# Cyber_VCM.net
KiCad netlist of a schematic drawn in Altium Designer
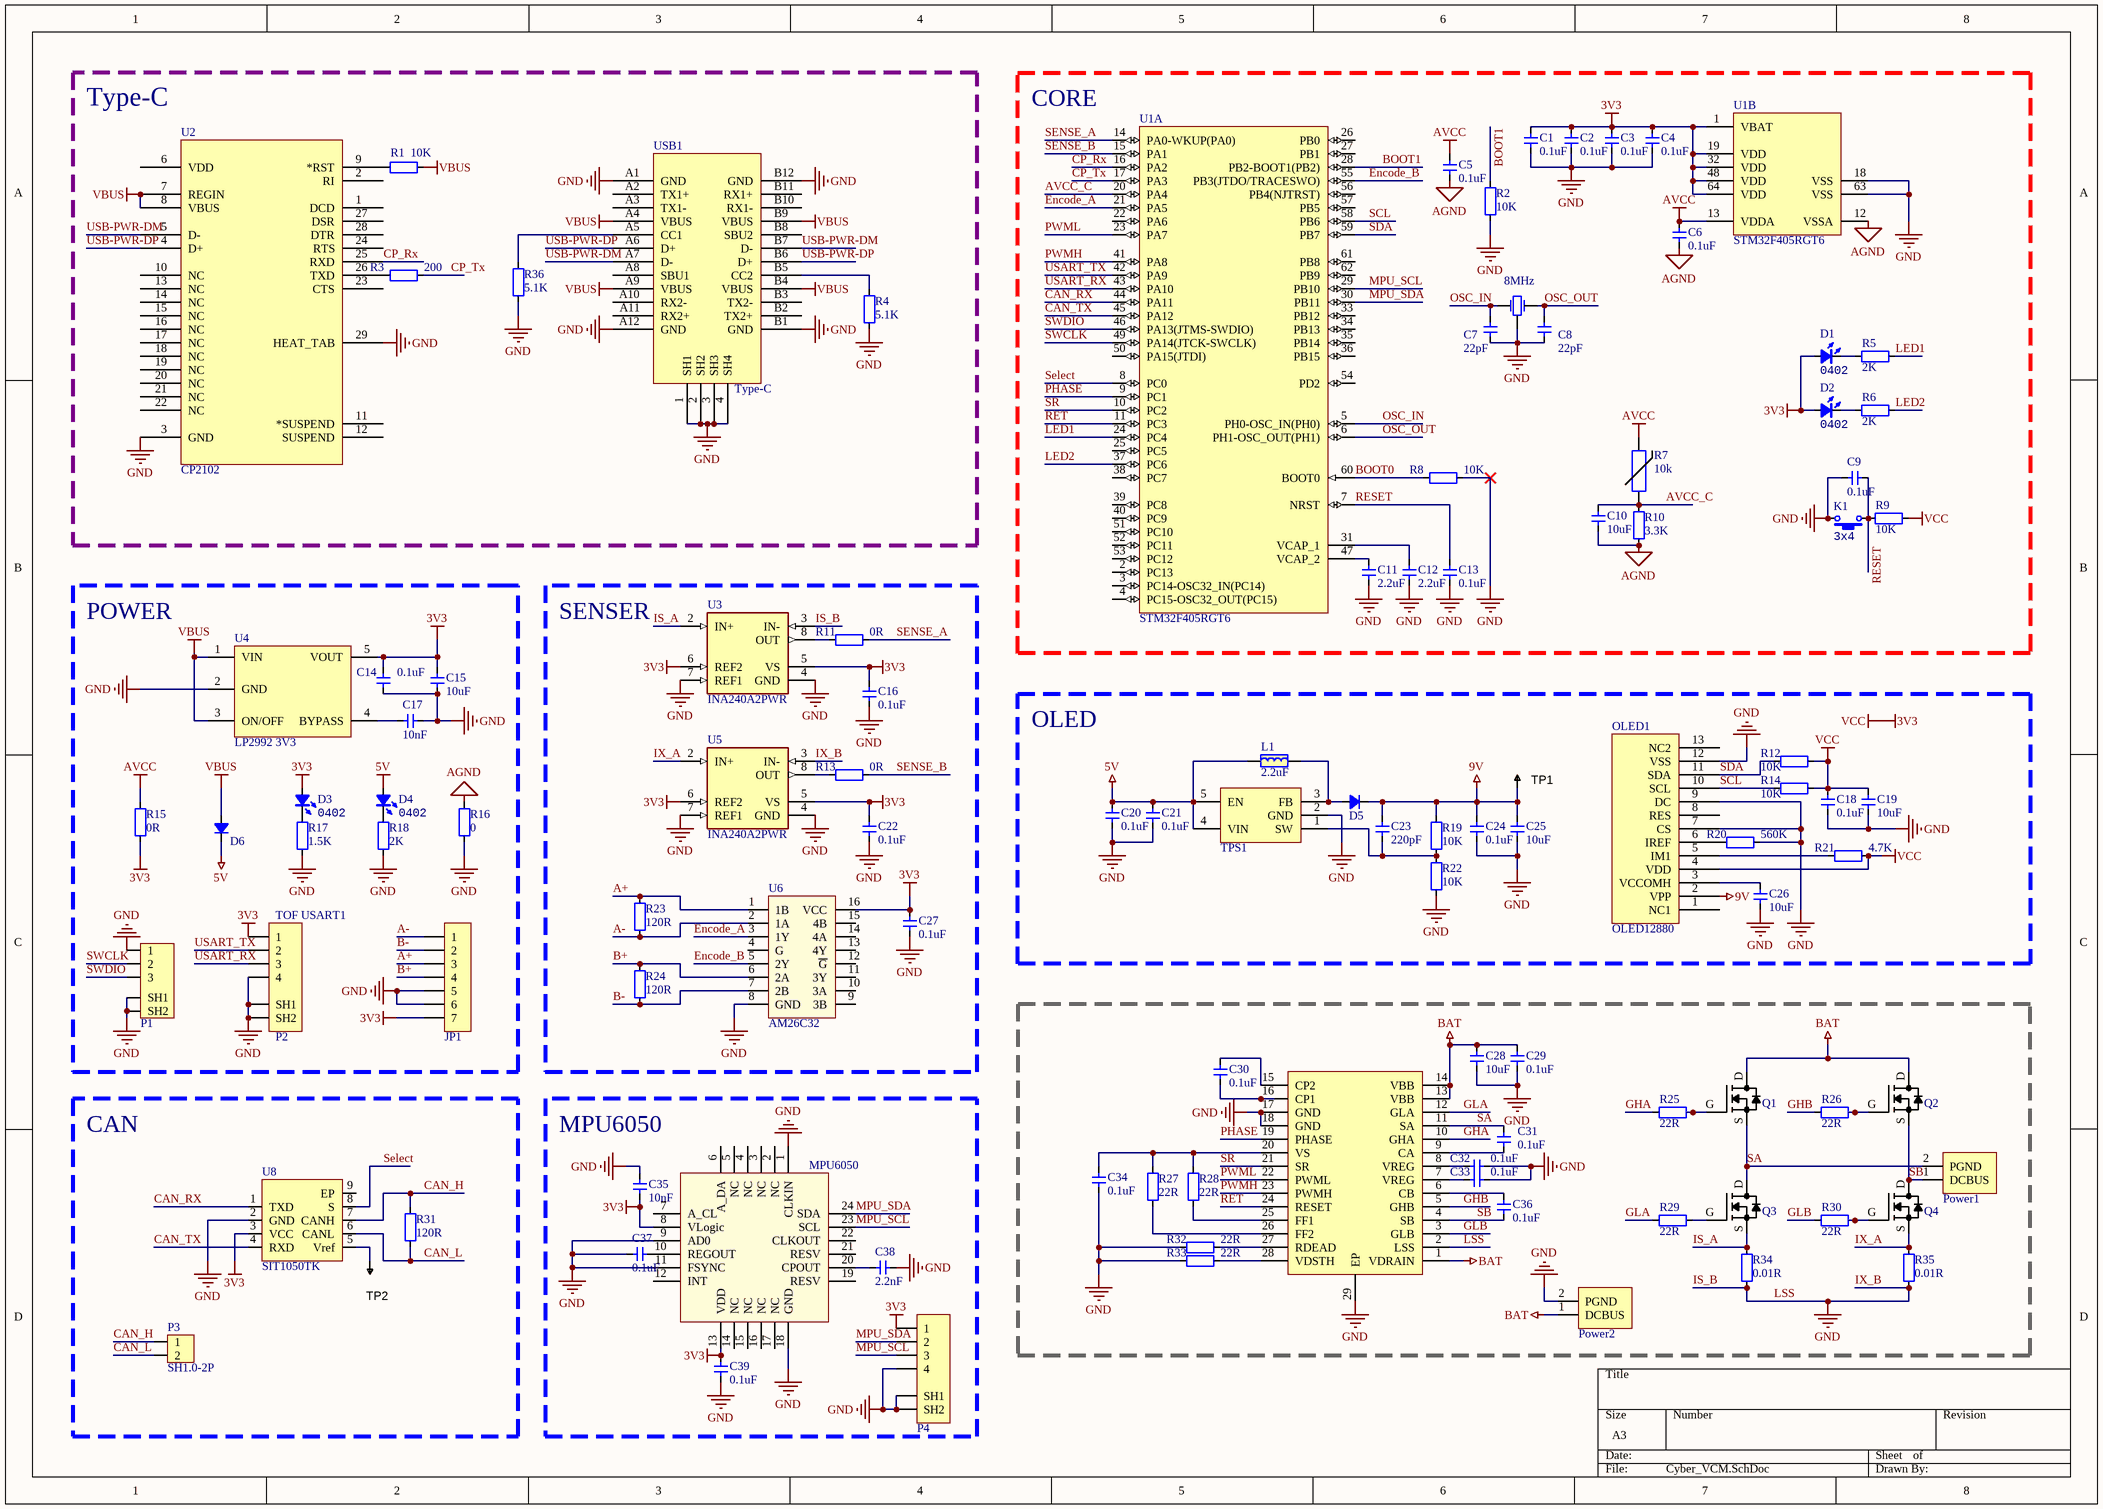
[diagram p0: Cyber_VCM.SchDoc]

(export (version "E")
  (design (tool "Eeschema 10.0.6"))
  (components
    (comp (ref "*1") (value "A3941") (footprint "TSSOP28_n") (libsource (lib "Cyber_VCM") (part "A3941")))
    (comp (ref "C1")
      (value "0.1uF")
      (footprint "CAP_0402")
      (description "Capacitor")
      (libsource (lib "VectorController") (part "电容-0402"))
    )
    (comp (ref "C2")
      (value "0.1uF")
      (footprint "CAP_0402")
      (description "Capacitor")
      (libsource (lib "VectorController") (part "电容-0402"))
    )
    (comp (ref "C3")
      (value "0.1uF")
      (footprint "CAP_0402")
      (description "Capacitor")
      (libsource (lib "VectorController") (part "电容-0402"))
    )
    (comp (ref "C4")
      (value "0.1uF")
      (footprint "CAP_0402")
      (description "Capacitor")
      (libsource (lib "VectorController") (part "电容-0402"))
    )
    (comp (ref "C5")
      (value "0.1uF")
      (footprint "0603-CAP")
      (description "Capacitor")
      (libsource (lib "Ctrl_FOC") (part "电容-0603"))
    )
    (comp (ref "C6")
      (value "0.1uF")
      (footprint "0603-CAP")
      (description "Capacitor")
      (libsource (lib "Ctrl_FOC") (part "电容-0603"))
    )
    (comp (ref "C7")
      (value "22pF")
      (footprint "CAP_0402")
      (description "Capacitor")
      (libsource (lib "Ctrl_FOC") (part "电容-0402"))
    )
    (comp (ref "C8")
      (value "22pF")
      (footprint "CAP_0402")
      (description "Capacitor")
      (libsource (lib "Ctrl_FOC") (part "电容-0402"))
    )
    (comp (ref "C9")
      (value "0.1uF")
      (footprint "CAP_0402")
      (description "Capacitor")
      (libsource (lib "VectorController") (part "电容-0402"))
    )
    (comp (ref "C10")
      (value "10uF")
      (footprint "CAP_0402")
      (description "Capacitor")
      (libsource (lib "MyPcbLib") (part "电容-0402"))
    )
    (comp (ref "C11")
      (value "2.2uF")
      (footprint "CAP_0402")
      (description "Capacitor")
      (libsource (lib "Ctrl_FOC") (part "电容-0402"))
    )
    (comp (ref "C12")
      (value "2.2uF")
      (footprint "CAP_0402")
      (description "Capacitor")
      (libsource (lib "Ctrl_FOC") (part "电容-0402"))
    )
    (comp (ref "C13")
      (value "0.1uF")
      (footprint "CAP_0402")
      (description "Capacitor")
      (libsource (lib "Ctrl_FOC") (part "电容-0402"))
    )
    (comp (ref "C14")
      (value "0.1uF")
      (footprint "CAP_0402")
      (description "Capacitor")
      (libsource (lib "Cyber_VCM") (part "电容-0402"))
    )
    (comp (ref "C15")
      (value "10uF")
      (footprint "CAP_0402")
      (description "Capacitor")
      (libsource (lib "Cyber_VCM") (part "电容-0402"))
    )
    (comp (ref "C16")
      (value "0.1uF")
      (footprint "CAP_0402")
      (description "Capacitor")
      (libsource (lib "MyPcbLib") (part "电容-0402"))
    )
    (comp (ref "C17")
      (value "10nF")
      (footprint "CAP_0402")
      (description "Capacitor")
      (libsource (lib "Cyber_VCM") (part "电容-0402"))
    )
    (comp (ref "C18")
      (value "0.1uF")
      (footprint "CAP_0402")
      (description "Capacitor")
      (libsource (lib "Serena-Ctrl") (part "电容-0402"))
    )
    (comp (ref "C19")
      (value "10uF")
      (footprint "CAP_0402")
      (description "Capacitor")
      (libsource (lib "Serena-Ctrl") (part "电容-0402"))
    )
    (comp (ref "C20")
      (value "0.1uF")
      (footprint "CAP_0402")
      (description "Capacitor")
      (libsource (lib "Serena-Ctrl") (part "电容-0402"))
    )
    (comp (ref "C21")
      (value "0.1uF")
      (footprint "CAP_0402")
      (description "Capacitor")
      (libsource (lib "Serena-Ctrl") (part "电容-0402"))
    )
    (comp (ref "C22")
      (value "0.1uF")
      (footprint "CAP_0402")
      (description "Capacitor")
      (libsource (lib "MyPcbLib") (part "电容-0402"))
    )
    (comp (ref "C23")
      (value "220pF")
      (footprint "CAP_0402")
      (description "Capacitor")
      (libsource (lib "Serena-Ctrl") (part "电容-0402"))
    )
    (comp (ref "C24")
      (value "0.1uF")
      (footprint "0603-CAP")
      (description "Capacitor")
      (libsource (lib "Serena-Ctrl") (part "电容-0603"))
    )
    (comp (ref "C25")
      (value "10uF")
      (footprint "0603-CAP")
      (description "Capacitor")
      (libsource (lib "Serena-Ctrl") (part "电容-0603"))
    )
    (comp (ref "C26")
      (value "10uF")
      (footprint "CAP_0402")
      (description "Capacitor")
      (libsource (lib "Serena-Ctrl") (part "电容-0402"))
    )
    (comp (ref "C27")
      (value "0.1uF")
      (footprint "0603-CAP")
      (description "Capacitor")
      (libsource (lib "VCM_Ctrl") (part "电容-0603"))
    )
    (comp (ref "C28")
      (value "10uF")
      (footprint "2520-L")
      (description "Capacitor")
      (libsource (lib "Cyber_VCM") (part "电容-1206"))
    )
    (comp (ref "C29")
      (value "0.1uF")
      (footprint "2520-L")
      (description "Capacitor")
      (libsource (lib "Cyber_VCM") (part "电容-1206"))
    )
    (comp (ref "C30")
      (value "0.1uF")
      (footprint "0603-CAP")
      (description "Capacitor")
      (libsource (lib "Cyber_VCM") (part "电容-0603"))
    )
    (comp (ref "C31")
      (value "0.1uF")
      (footprint "CAP_0402")
      (description "Capacitor")
      (libsource (lib "Cyber_VCM") (part "电容-0402"))
    )
    (comp (ref "C32")
      (value "0.1uF")
      (footprint "CAP_0402")
      (description "Capacitor")
      (libsource (lib "Cyber_VCM") (part "电容-0402"))
    )
    (comp (ref "C33")
      (value "0.1uF")
      (footprint "CAP_0402")
      (description "Capacitor")
      (libsource (lib "Cyber_VCM") (part "电容-0402"))
    )
    (comp (ref "C34")
      (value "0.1uF")
      (footprint "0603-CAP")
      (description "Capacitor")
      (libsource (lib "Cyber_VCM") (part "电容-0603"))
    )
    (comp (ref "C35")
      (value "10nF")
      (footprint "CAP_0402")
      (description "Capacitor")
      (libsource (lib "MyPcbLib") (part "电容-0402"))
    )
    (comp (ref "C36")
      (value "0.1uF")
      (footprint "CAP_0402")
      (description "Capacitor")
      (libsource (lib "Cyber_VCM") (part "电容-0402"))
    )
    (comp (ref "C37")
      (value "0.1uF")
      (footprint "CAP_0402")
      (description "Capacitor")
      (libsource (lib "MyPcbLib") (part "电容-0402"))
    )
    (comp (ref "C38")
      (value "2.2nF")
      (footprint "CAP_0402")
      (description "Capacitor")
      (libsource (lib "MyPcbLib") (part "电容-0402"))
    )
    (comp (ref "C39")
      (value "0.1uF")
      (footprint "CAP_0402")
      (description "Capacitor")
      (libsource (lib "MyPcbLib") (part "电容-0402"))
    )
    (comp (ref "D1")
      (value "color?")
      (footprint "LED_0402_BLUE")
      (description "LED")
      (fields (field (name "TYPE") "0402"))
      (libsource (lib "Cyber_VCM") (part "LED_0402"))
    )
    (comp (ref "D2")
      (value "color?")
      (footprint "LED_0402_BLUE")
      (description "LED")
      (fields (field (name "TYPE") "0402"))
      (libsource (lib "Cyber_VCM") (part "LED_0402"))
    )
    (comp (ref "D3")
      (value "color?")
      (footprint "LED_0402_BLUE")
      (description "LED")
      (fields (field (name "TYPE") "0402"))
      (libsource (lib "") (part "LED_0402_1"))
    )
    (comp (ref "D4")
      (value "color?")
      (footprint "LED_0402_BLUE")
      (description "LED")
      (fields (field (name "TYPE") "0402"))
      (libsource (lib "") (part "LED_0402_1"))
    )
    (comp (ref "D5")
      (value "二极管-5819W")
      (footprint "SOD-123")
      (description "40V")
      (libsource (lib "Cyber_VCM") (part "二极管-5819W"))
    )
    (comp (ref "D6")
      (value "二极管-5819W")
      (footprint "SOD-123")
      (description "40V")
      (libsource (lib "Cyber_VCM") (part "二极管-5819W"))
    )
    (comp (ref "JP1")
      (value "SH1.0-7P")
      (footprint "SH1.0-7P-L")
      (libsource (lib "Cyber_VCM") (part "SH1.0-7P"))
    )
    (comp (ref "K1")
      (value "3x4")
      (footprint "ButtonTACT_3x4x2_180")
      (description "Button")
      (fields (field (name "Comment") "TACT 2P"))
      (libsource (lib "Ctrl_FOC") (part "ButtonTACT_3x4x2_180"))
    )
    (comp (ref "L1")
      (value "2.2uF")
      (footprint "2520-L")
      (description "磁珠")
      (libsource (lib "Serena-Ctrl") (part "电感-0805"))
    )
    (comp (ref "OLED1")
      (value "OLED12880")
      (footprint "OLED12880")
      (description "12880寸OLED")
      (libsource (lib "Serena-Ctrl") (part "OLED12880"))
    )
    (comp (ref "P1")
      (value "SH1.0-3P")
      (footprint "SH1.0-3P")
      (description "Header")
      (libsource (lib "Cyber_VCM") (part "SH1.0-3P"))
    )
    (comp (ref "P2")
      (value "TOF USART1")
      (footprint "SH1.0-4P")
      (libsource (lib "Cyber_VCM") (part "SH1.0-4P"))
    )
    (comp (ref "P3")
      (value "SH1.0-2P")
      (footprint "SH1.0-2P")
      (libsource (lib "Cyber_VCM") (part "SH1.0-2P"))
    )
    (comp (ref "P4")
      (value "SH1.0-4P")
      (footprint "SH1.0-4P")
      (libsource (lib "Cyber_VCM") (part "SH1.0-4P"))
    )
    (comp (ref "Power1")
      (value "电源")
      (footprint "音圈电机电源接口")
      (description "12~24VDC电源")
      (libsource (lib "Cyber_VCM") (part "电源"))
    )
    (comp (ref "Power2")
      (value "电源")
      (footprint "TX60电源")
      (description "12~24VDC电源")
      (libsource (lib "Cyber_VCM") (part "电源"))
    )
    (comp (ref "Q1")
      (value "NTMFS4935NT1G")
      (footprint "SO8FL")
      (description "MOSFET N-CH 30V 13A SO8FL")
      (fields (field (name "MANUFACTURER") "ON Semiconductor"))
      (libsource (lib "Cyber_VCM") (part "NTMFS4935NT1G"))
    )
    (comp (ref "Q2")
      (value "NTMFS4935NT1G")
      (footprint "SO8FL")
      (description "MOSFET N-CH 30V 13A SO8FL")
      (fields (field (name "MANUFACTURER") "ON Semiconductor"))
      (libsource (lib "Cyber_VCM") (part "NTMFS4935NT1G"))
    )
    (comp (ref "Q3")
      (value "NTMFS4935NT1G")
      (footprint "SO8FL")
      (description "MOSFET N-CH 30V 13A SO8FL")
      (fields (field (name "MANUFACTURER") "ON Semiconductor"))
      (libsource (lib "Cyber_VCM") (part "NTMFS4935NT1G"))
    )
    (comp (ref "Q4")
      (value "NTMFS4935NT1G")
      (footprint "SO8FL")
      (description "MOSFET N-CH 30V 13A SO8FL")
      (fields (field (name "MANUFACTURER") "ON Semiconductor"))
      (libsource (lib "Cyber_VCM") (part "NTMFS4935NT1G"))
    )
    (comp (ref "R1")
      (value "10K")
      (footprint "RES_0402")
      (description "Resistor")
      (libsource (lib "MyPcbLib") (part "电阻-0402"))
    )
    (comp (ref "R2")
      (value "10K")
      (footprint "RES_0402")
      (description "Resistor")
      (libsource (lib "") (part "电阻-0402_1"))
    )
    (comp (ref "R3")
      (value "200")
      (footprint "RES_0402")
      (description "Resistor")
      (libsource (lib "MyPcbLib") (part "电阻-0402"))
    )
    (comp (ref "R4")
      (value "5.1K")
      (footprint "RES_0402")
      (description "Resistor")
      (libsource (lib "") (part "电阻-0402_1"))
    )
    (comp (ref "R5")
      (value "2K")
      (footprint "RES_0402")
      (description "Resistor")
      (libsource (lib "") (part "电阻-0402_1"))
    )
    (comp (ref "R6")
      (value "2K")
      (footprint "RES_0402")
      (description "Resistor")
      (libsource (lib "") (part "电阻-0402_1"))
    )
    (comp (ref "R7")
      (value "10k")
      (footprint "RES_0402")
      (description "THERMISTOR 10K OHM NTC 0402 SMD")
      (fields (field (name "Comment") "NCP15XH103F03RC"))
      (libsource (lib "MyPcbLib") (part "NCP15XH103F03RC"))
    )
    (comp (ref "R8")
      (value "10K")
      (footprint "RES_0402")
      (description "Resistor")
      (libsource (lib "Ctrl_FOC") (part "电阻-0402"))
    )
    (comp (ref "R9")
      (value "10K")
      (footprint "RES_0402")
      (description "Resistor")
      (libsource (lib "Ctrl_FOC") (part "电阻-0402"))
    )
    (comp (ref "R10")
      (value "3.3K")
      (footprint "RES_0402")
      (description "Resistor")
      (libsource (lib "") (part "电阻-0402_3"))
    )
    (comp (ref "R11")
      (value "0R")
      (footprint "RES_0402")
      (description "Resistor")
      (libsource (lib "") (part "电阻-0402_2"))
    )
    (comp (ref "R12")
      (value "10K")
      (footprint "RES_0402")
      (description "Resistor")
      (libsource (lib "") (part "电阻-0402_1"))
    )
    (comp (ref "R13")
      (value "0R")
      (footprint "RES_0402")
      (description "Resistor")
      (libsource (lib "") (part "电阻-0402_2"))
    )
    (comp (ref "R14")
      (value "10K")
      (footprint "RES_0402")
      (description "Resistor")
      (libsource (lib "") (part "电阻-0402_1"))
    )
    (comp (ref "R15")
      (value "0R")
      (footprint "RES_0402")
      (description "Resistor")
      (libsource (lib "") (part "电阻-0402_1"))
    )
    (comp (ref "R16")
      (value "0")
      (footprint "RES_0402")
      (description "Resistor")
      (libsource (lib "") (part "电阻-0402_2"))
    )
    (comp (ref "R17")
      (value "1.5K")
      (footprint "RES_0402")
      (description "Resistor")
      (libsource (lib "") (part "电阻-0402_2"))
    )
    (comp (ref "R18")
      (value "2K")
      (footprint "RES_0402")
      (description "Resistor")
      (libsource (lib "") (part "电阻-0402_2"))
    )
    (comp (ref "R19")
      (value "10K")
      (footprint "RES_0402")
      (description "Resistor")
      (libsource (lib "Serena-Ctrl") (part "电阻-0402"))
    )
    (comp (ref "R20")
      (value "560K")
      (footprint "RES_0402")
      (description "Resistor")
      (libsource (lib "") (part "电阻-0402_1"))
    )
    (comp (ref "R21")
      (value "4.7K")
      (footprint "RES_0402")
      (description "Resistor")
      (libsource (lib "") (part "电阻-0402_1"))
    )
    (comp (ref "R22")
      (value "10K")
      (footprint "RES_0402")
      (description "Resistor")
      (libsource (lib "Serena-Ctrl") (part "电阻-0402"))
    )
    (comp (ref "R23")
      (value "120R")
      (footprint "RES_0603")
      (description "Resistor")
      (libsource (lib "Ctrl_FOC") (part "电阻-0603"))
    )
    (comp (ref "R24")
      (value "120R")
      (footprint "RES_0603")
      (description "Resistor")
      (libsource (lib "Ctrl_FOC") (part "电阻-0603"))
    )
    (comp (ref "R25")
      (value "22R")
      (footprint "RES_0402")
      (description "Resistor")
      (libsource (lib "") (part "电阻-0402_1"))
    )
    (comp (ref "R26")
      (value "22R")
      (footprint "RES_0402")
      (description "Resistor")
      (libsource (lib "") (part "电阻-0402_1"))
    )
    (comp (ref "R27")
      (value "22R")
      (footprint "RES_0402")
      (description "Resistor")
      (libsource (lib "Cyber_VCM") (part "电阻-0402"))
    )
    (comp (ref "R28")
      (value "22R")
      (footprint "RES_0402")
      (description "Resistor")
      (libsource (lib "Cyber_VCM") (part "电阻-0402"))
    )
    (comp (ref "R29")
      (value "22R")
      (footprint "RES_0402")
      (description "Resistor")
      (libsource (lib "") (part "电阻-0402_1"))
    )
    (comp (ref "R30")
      (value "22R")
      (footprint "RES_0402")
      (description "Resistor")
      (libsource (lib "") (part "电阻-0402_1"))
    )
    (comp (ref "R31")
      (value "120R")
      (footprint "RES_0402")
      (description "Resistor")
      (libsource (lib "Cyber_VCM") (part "电阻-0402"))
    )
    (comp (ref "R32")
      (value "22R")
      (footprint "RES_0402")
      (description "Resistor")
      (libsource (lib "") (part "电阻-0402_1"))
    )
    (comp (ref "R33")
      (value "22R")
      (footprint "RES_0402")
      (description "Resistor")
      (libsource (lib "") (part "电阻-0402_1"))
    )
    (comp (ref "R34")
      (value "0.01R")
      (footprint "1206-RES")
      (description "Resistor")
      (libsource (lib "Cyber_VCM") (part "电阻-1206"))
    )
    (comp (ref "R35")
      (value "0.01R")
      (footprint "1206-RES")
      (description "Resistor")
      (libsource (lib "Cyber_VCM") (part "电阻-1206"))
    )
    (comp (ref "R36")
      (value "5.1K")
      (footprint "RES_0402")
      (description "Resistor")
      (libsource (lib "") (part "电阻-0402_1"))
    )
    (comp (ref "TP1")
      (value "TESTPOINT")
      (footprint "TP-R30")
      (description "SMD test pin")
      (libsource (lib "Serena-Ctrl") (part "TESTPOINT"))
    )
    (comp (ref "TP2")
      (value "TESTPOINT")
      (footprint "TP-R30")
      (description "SMD test pin")
      (libsource (lib "Serena-Ctrl") (part "TESTPOINT"))
    )
    (comp (ref "TPS1")
      (value "TPS61040DBV")
      (footprint "SOT23-5")
      (libsource (lib "Serena-Ctrl") (part "TPS61040DBV"))
    )
    (comp (ref "U1")
      (value "STM32F405RGT6")
      (footprint "主控芯片LQFP64-10*10")
      (fields (field (name "MANUFACTURER") "STMicroelectronics"))
      (libsource (lib "VectorController") (part "STM32F405RGT6"))
    )
    (comp (ref "U2")
      (value "CP2102")
      (footprint "QFN-28")
      (description "USB转TTL")
      (libsource (lib "Cyber_VCM") (part "CP2102"))
    )
    (comp (ref "U3")
      (value "INA240A2PWR")
      (footprint "SOP65 P640X120-8N")
      (fields (field (name "MF") "Texas Instruments"))
      (libsource (lib "mLib") (part "INA240A2PWR"))
    )
    (comp (ref "U4")
      (value "LP2992 3V3")
      (footprint "SOT23-5")
      (description "LDO")
      (libsource (lib "Cyber_VCM") (part "LP2992"))
    )
    (comp (ref "U5")
      (value "INA240A2PWR")
      (footprint "SOP65 P640X120-8N")
      (fields (field (name "MF") "Texas Instruments"))
      (libsource (lib "mLib") (part "INA240A2PWR"))
    )
    (comp (ref "U6")
      (value "AM26C32")
      (footprint "SOP16")
      (description "AM26C32 Quadruple Differential Line Receiver")
      (libsource (lib "VCM_Ctrl") (part "AM26C32"))
    )
    (comp (ref "U7")
      (value "MPU6050")
      (footprint "QFN-24")
      (description "六轴传感器")
      (libsource (lib "mLib") (part "MPU6050"))
    )
    (comp (ref "U8")
      (value "SIT1050TK")
      (footprint "DFN3x3-8")
      (description "CAN收发器，DFN3x3-8")
      (libsource (lib "Cyber_VCM") (part "SIT1050TK"))
    )
    (comp (ref "USB1")
      (value "Type-C")
      (footprint "Type-C-TOP")
      (libsource (lib "Cyber_VCM") (part "USB-Type-C-TOP"))
    )
    (comp (ref "X1") (value "8MHz") (footprint "晶振-3P") (libsource (lib "MiniFly ") (part "XTAL-3215")))
  )
  (nets
    (net (code "1") (name "/A+") (class "Default")
      (node (ref "JP1") (pin "3") (pinfunction "3_3") (pintype "passive"))
      (node (ref "R23") (pin "2") (pinfunction "2_2") (pintype "passive"))
      (node (ref "U6") (pin "1") (pinfunction "1B_1") (pintype "passive"))
    )
    (net (code "2") (name "/A-") (class "Default")
      (node (ref "JP1") (pin "1") (pinfunction "1_1") (pintype "passive"))
      (node (ref "R23") (pin "1") (pinfunction "1_1") (pintype "passive"))
      (node (ref "U6") (pin "2") (pinfunction "1A_2") (pintype "passive"))
    )
    (net (code "3") (name "/AVCC_C") (class "Default")
      (node (ref "C10") (pin "2") (pinfunction "2_2") (pintype "passive"))
      (node (ref "R10") (pin "2") (pinfunction "2_2") (pintype "passive"))
      (node (ref "R7") (pin "1") (pinfunction "0_1") (pintype "passive"))
      (node (ref "U1") (pin "20") (pinfunction "PA4_20") (pintype "bidirectional"))
    )
    (net (code "4") (name "/B+") (class "Default")
      (node (ref "JP1") (pin "4") (pinfunction "4_4") (pintype "passive"))
      (node (ref "R24") (pin "2") (pinfunction "2_2") (pintype "passive"))
      (node (ref "U6") (pin "6") (pinfunction "2A_6") (pintype "passive"))
    )
    (net (code "5") (name "/B-") (class "Default")
      (node (ref "JP1") (pin "2") (pinfunction "2_2") (pintype "passive"))
      (node (ref "R24") (pin "1") (pinfunction "1_1") (pintype "passive"))
      (node (ref "U6") (pin "7") (pinfunction "2B_7") (pintype "passive"))
    )
    (net (code "6") (name "/BOOT0") (class "Default")
      (node (ref "R8") (pin "2") (pinfunction "2_2") (pintype "passive"))
      (node (ref "U1") (pin "60") (pinfunction "BOOT0_60") (pintype "input"))
    )
    (net (code "7") (name "/BOOT1") (class "Default")
      (node (ref "R2") (pin "2") (pinfunction "2_2") (pintype "passive"))
      (node (ref "U1") (pin "28") (pinfunction "PB2-BOOT1(PB2)_28") (pintype "bidirectional"))
    )
    (net (code "8") (name "/CAN_H") (class "Default")
      (node (ref "P3") (pin "1") (pinfunction "1_1") (pintype "passive"))
      (node (ref "R31") (pin "2") (pinfunction "2_2") (pintype "passive"))
      (node (ref "U8") (pin "7") (pinfunction "CANH_7") (pintype "passive"))
    )
    (net (code "9") (name "/CAN_L") (class "Default")
      (node (ref "P3") (pin "2") (pinfunction "2_2") (pintype "passive"))
      (node (ref "R31") (pin "1") (pinfunction "1_1") (pintype "passive"))
      (node (ref "U8") (pin "6") (pinfunction "CANL_6") (pintype "passive"))
    )
    (net (code "10") (name "/CAN_RX") (class "Default")
      (node (ref "U1") (pin "44") (pinfunction "PA11_44") (pintype "bidirectional"))
      (node (ref "U8") (pin "1") (pinfunction "TXD_1") (pintype "passive"))
    )
    (net (code "11") (name "/CAN_TX") (class "Default")
      (node (ref "U1") (pin "45") (pinfunction "PA12_45") (pintype "bidirectional"))
      (node (ref "U8") (pin "4") (pinfunction "RXD_4") (pintype "passive"))
    )
    (net (code "12") (name "/CP_Rx") (class "Default")
      (node (ref "U1") (pin "16") (pinfunction "PA2_16") (pintype "bidirectional"))
      (node (ref "U2") (pin "25") (pinfunction "RXD_25") (pintype "passive"))
    )
    (net (code "13") (name "/CP_Tx") (class "Default")
      (node (ref "R3") (pin "1") (pinfunction "1_1") (pintype "passive"))
      (node (ref "U1") (pin "17") (pinfunction "PA3_17") (pintype "bidirectional"))
    )
    (net (code "14") (name "/Encode_A") (class "Default")
      (node (ref "U1") (pin "21") (pinfunction "PA5_21") (pintype "bidirectional"))
      (node (ref "U6") (pin "3") (pinfunction "1Y_3") (pintype "passive"))
    )
    (net (code "15") (name "/Encode_B") (class "Default")
      (node (ref "U1") (pin "55") (pinfunction "PB3(JTDO/TRACESWO)_55") (pintype "bidirectional"))
      (node (ref "U6") (pin "5") (pinfunction "2Y_5") (pintype "passive"))
    )
    (net (code "16") (name "/GHA") (class "Default")
      (node (ref "*1") (pin "10") (pinfunction "GHA_10") (pintype "passive"))
      (node (ref "R25") (pin "1") (pinfunction "1_1") (pintype "passive"))
    )
    (net (code "17") (name "/GHB") (class "Default")
      (node (ref "*1") (pin "5") (pinfunction "GHB_5") (pintype "passive"))
      (node (ref "R26") (pin "1") (pinfunction "1_1") (pintype "passive"))
    )
    (net (code "18") (name "/GLA") (class "Default")
      (node (ref "*1") (pin "12") (pinfunction "GLA_12") (pintype "passive"))
      (node (ref "R29") (pin "1") (pinfunction "1_1") (pintype "passive"))
    )
    (net (code "19") (name "/GLB") (class "Default")
      (node (ref "*1") (pin "3") (pinfunction "GLB_3") (pintype "passive"))
      (node (ref "R30") (pin "1") (pinfunction "1_1") (pintype "passive"))
    )
    (net (code "20") (name "/IS_A") (class "Default")
      (node (ref "Q3") (pin "S") (pinfunction "S_S") (pintype "passive"))
      (node (ref "R34") (pin "2") (pinfunction "2_2") (pintype "passive"))
      (node (ref "U3") (pin "2") (pinfunction "IN+_2") (pintype "input"))
    )
    (net (code "21") (name "/IX_A") (class "Default")
      (node (ref "Q4") (pin "S") (pinfunction "S_S") (pintype "passive"))
      (node (ref "R35") (pin "2") (pinfunction "2_2") (pintype "passive"))
      (node (ref "U5") (pin "2") (pinfunction "IN+_2") (pintype "input"))
    )
    (net (code "22") (name "/LED1") (class "Default")
      (node (ref "R5") (pin "2") (pinfunction "2_2") (pintype "passive"))
      (node (ref "U1") (pin "24") (pinfunction "PC4_24") (pintype "bidirectional"))
    )
    (net (code "23") (name "/LED2") (class "Default")
      (node (ref "R6") (pin "2") (pinfunction "2_2") (pintype "passive"))
      (node (ref "U1") (pin "37") (pinfunction "PC6_37") (pintype "bidirectional"))
    )
    (net (code "24") (name "/MPU_SCL") (class "Default")
      (node (ref "P4") (pin "3") (pinfunction "3_3") (pintype "passive"))
      (node (ref "U1") (pin "29") (pinfunction "PB10_29") (pintype "bidirectional"))
      (node (ref "U7") (pin "23") (pinfunction "SCL_23") (pintype "passive"))
    )
    (net (code "25") (name "/MPU_SDA") (class "Default")
      (node (ref "P4") (pin "2") (pinfunction "2_2") (pintype "passive"))
      (node (ref "U1") (pin "30") (pinfunction "PB11_30") (pintype "bidirectional"))
      (node (ref "U7") (pin "24") (pinfunction "SDA_24") (pintype "passive"))
    )
    (net (code "26") (name "/OSC_IN") (class "Default")
      (node (ref "C7") (pin "2") (pinfunction "2_2") (pintype "passive"))
      (node (ref "U1") (pin "5") (pinfunction "PH0-OSC_IN(PH0)_5") (pintype "bidirectional"))
      (node (ref "X1") (pin "1") (pinfunction "OSC1_1") (pintype "passive"))
    )
    (net (code "27") (name "/OSC_OUT") (class "Default")
      (node (ref "C8") (pin "2") (pinfunction "2_2") (pintype "passive"))
      (node (ref "U1") (pin "6") (pinfunction "PH1-OSC_OUT(PH1)_6") (pintype "bidirectional"))
      (node (ref "X1") (pin "3") (pinfunction "OSC2_3") (pintype "passive"))
    )
    (net (code "28") (name "/PHASE") (class "Default")
      (node (ref "*1") (pin "19") (pinfunction "PHASE_19") (pintype "passive"))
      (node (ref "U1") (pin "9") (pinfunction "PC1_9") (pintype "bidirectional"))
    )
    (net (code "29") (name "/PWMH") (class "Default")
      (node (ref "*1") (pin "23") (pinfunction "PWMH_23") (pintype "passive"))
      (node (ref "U1") (pin "41") (pinfunction "PA8_41") (pintype "bidirectional"))
    )
    (net (code "30") (name "/PWML") (class "Default")
      (node (ref "*1") (pin "22") (pinfunction "PWML_22") (pintype "passive"))
      (node (ref "U1") (pin "23") (pinfunction "PA7_23") (pintype "bidirectional"))
    )
    (net (code "31") (name "/RESET") (class "Default")
      (node (ref "C13") (pin "1") (pinfunction "1_1") (pintype "passive"))
      (node (ref "C9") (pin "2") (pinfunction "2_2") (pintype "passive"))
      (node (ref "K1") (pin "1") (pinfunction "1_1") (pintype "passive"))
      (node (ref "R9") (pin "2") (pinfunction "2_2") (pintype "passive"))
      (node (ref "U1") (pin "7") (pinfunction "NRST_7") (pintype "bidirectional"))
    )
    (net (code "32") (name "/RET") (class "Default")
      (node (ref "*1") (pin "24") (pinfunction "RESET_24") (pintype "passive"))
      (node (ref "U1") (pin "11") (pinfunction "PC3_11") (pintype "bidirectional"))
    )
    (net (code "33") (name "/SA") (class "Default")
      (node (ref "*1") (pin "11") (pinfunction "SA_11") (pintype "passive"))
      (node (ref "C31") (pin "2") (pinfunction "2_2") (pintype "passive"))
      (node (ref "Power1") (pin "2") (pinfunction "PGND_2") (pintype "passive"))
      (node (ref "Q1") (pin "S") (pinfunction "S_S") (pintype "passive"))
      (node (ref "Q3") (pin "D") (pinfunction "D_D") (pintype "passive"))
    )
    (net (code "34") (name "/SB") (class "Default")
      (node (ref "*1") (pin "4") (pinfunction "SB_4") (pintype "passive"))
      (node (ref "C36") (pin "1") (pinfunction "1_1") (pintype "passive"))
      (node (ref "Power1") (pin "1") (pinfunction "DCBUS_1") (pintype "passive"))
      (node (ref "Q2") (pin "S") (pinfunction "S_S") (pintype "passive"))
      (node (ref "Q4") (pin "D") (pinfunction "D_D") (pintype "passive"))
    )
    (net (code "35") (name "/SCL") (class "Default")
      (node (ref "OLED1") (pin "10") (pinfunction "SCL_10") (pintype "passive"))
      (node (ref "R14") (pin "1") (pinfunction "1_1") (pintype "passive"))
      (node (ref "U1") (pin "58") (pinfunction "PB6_58") (pintype "bidirectional"))
    )
    (net (code "36") (name "/SDA") (class "Default")
      (node (ref "OLED1") (pin "11") (pinfunction "SDA_11") (pintype "passive"))
      (node (ref "R12") (pin "1") (pinfunction "1_1") (pintype "passive"))
      (node (ref "U1") (pin "59") (pinfunction "PB7_59") (pintype "bidirectional"))
    )
    (net (code "37") (name "/SENSE_A") (class "Default")
      (node (ref "R11") (pin "2") (pinfunction "2_2") (pintype "passive"))
      (node (ref "U1") (pin "14") (pinfunction "PA0-WKUP(PA0)_14") (pintype "bidirectional"))
    )
    (net (code "38") (name "/SENSE_B") (class "Default")
      (node (ref "R13") (pin "2") (pinfunction "2_2") (pintype "passive"))
      (node (ref "U1") (pin "15") (pinfunction "PA1_15") (pintype "bidirectional"))
    )
    (net (code "39") (name "/SR") (class "Default")
      (node (ref "*1") (pin "21") (pinfunction "SR_21") (pintype "passive"))
      (node (ref "U1") (pin "10") (pinfunction "PC2_10") (pintype "bidirectional"))
    )
    (net (code "40") (name "/SWCLK") (class "Default")
      (node (ref "P1") (pin "2") (pinfunction "2_2") (pintype "passive"))
      (node (ref "U1") (pin "49") (pinfunction "PA14(JTCK-SWCLK)_49") (pintype "bidirectional"))
    )
    (net (code "41") (name "/SWDIO") (class "Default")
      (node (ref "P1") (pin "3") (pinfunction "3_3") (pintype "passive"))
      (node (ref "U1") (pin "46") (pinfunction "PA13(JTMS-SWDIO)_46") (pintype "bidirectional"))
    )
    (net (code "42") (name "/Select") (class "Default")
      (node (ref "U1") (pin "8") (pinfunction "PC0_8") (pintype "bidirectional"))
      (node (ref "U8") (pin "8") (pinfunction "S_8") (pintype "passive"))
    )
    (net (code "43") (name "/USART_RX") (class "Default")
      (node (ref "P2") (pin "3") (pinfunction "3_3") (pintype "passive"))
      (node (ref "U1") (pin "43") (pinfunction "PA10_43") (pintype "bidirectional"))
    )
    (net (code "44") (name "/USART_TX") (class "Default")
      (node (ref "P2") (pin "2") (pinfunction "2_2") (pintype "passive"))
      (node (ref "U1") (pin "42") (pinfunction "PA9_42") (pintype "bidirectional"))
    )
    (net (code "45") (name "/USB-PWR-DM") (class "Default")
      (node (ref "U2") (pin "5") (pinfunction "D-_5") (pintype "passive"))
      (node (ref "USB1") (pin "A7") (pinfunction "D-_A7") (pintype "passive"))
      (node (ref "USB1") (pin "B7") (pinfunction "D-_B7") (pintype "passive"))
    )
    (net (code "46") (name "/USB-PWR-DP") (class "Default")
      (node (ref "U2") (pin "4") (pinfunction "D+_4") (pintype "passive"))
      (node (ref "USB1") (pin "A6") (pinfunction "D+_A6") (pintype "passive"))
      (node (ref "USB1") (pin "B6") (pinfunction "D+_B6") (pintype "passive"))
    )
    (net (code "47") (name "3V3") (class "Default")
      (node (ref "C1") (pin "2") (pinfunction "2_2") (pintype "passive"))
      (node (ref "C14") (pin "2") (pinfunction "2_2") (pintype "passive"))
      (node (ref "C15") (pin "2") (pinfunction "2_2") (pintype "passive"))
      (node (ref "C16") (pin "2") (pinfunction "2_2") (pintype "passive"))
      (node (ref "C18") (pin "2") (pinfunction "2_2") (pintype "passive"))
      (node (ref "C19") (pin "2") (pinfunction "2_2") (pintype "passive"))
      (node (ref "C2") (pin "2") (pinfunction "2_2") (pintype "passive"))
      (node (ref "C22") (pin "2") (pinfunction "2_2") (pintype "passive"))
      (node (ref "C27") (pin "2") (pinfunction "2_2") (pintype "passive"))
      (node (ref "C3") (pin "2") (pinfunction "2_2") (pintype "passive"))
      (node (ref "C35") (pin "1") (pinfunction "1_1") (pintype "passive"))
      (node (ref "C39") (pin "2") (pinfunction "2_2") (pintype "passive"))
      (node (ref "C4") (pin "2") (pinfunction "2_2") (pintype "passive"))
      (node (ref "D1") (pin "1") (pinfunction "A_1") (pintype "passive"))
      (node (ref "D2") (pin "1") (pinfunction "A_1") (pintype "passive"))
      (node (ref "D3") (pin "1") (pinfunction "A_1") (pintype "passive"))
      (node (ref "JP1") (pin "7") (pinfunction "7_7") (pintype "passive"))
      (node (ref "OLED1") (pin "4") (pinfunction "VDD_4") (pintype "passive"))
      (node (ref "P2") (pin "1") (pinfunction "1_1") (pintype "passive"))
      (node (ref "P4") (pin "1") (pinfunction "1_1") (pintype "passive"))
      (node (ref "R12") (pin "2") (pinfunction "2_2") (pintype "passive"))
      (node (ref "R14") (pin "2") (pinfunction "2_2") (pintype "passive"))
      (node (ref "R15") (pin "2") (pinfunction "2_2") (pintype "passive"))
      (node (ref "R21") (pin "2") (pinfunction "2_2") (pintype "passive"))
      (node (ref "R9") (pin "1") (pinfunction "1_1") (pintype "passive"))
      (node (ref "U1") (pin "1") (pinfunction "VBAT_1") (pintype "power_in"))
      (node (ref "U1") (pin "19") (pinfunction "VDD_19") (pintype "power_in"))
      (node (ref "U1") (pin "32") (pinfunction "VDD_32") (pintype "power_in"))
      (node (ref "U1") (pin "48") (pinfunction "VDD_48") (pintype "power_in"))
      (node (ref "U1") (pin "64") (pinfunction "VDD_64") (pintype "power_in"))
      (node (ref "U3") (pin "5") (pinfunction "VS_5") (pintype "power_in"))
      (node (ref "U3") (pin "6") (pinfunction "REF2_6") (pintype "input"))
      (node (ref "U4") (pin "5") (pinfunction "VOUT_5") (pintype "passive"))
      (node (ref "U5") (pin "5") (pinfunction "VS_5") (pintype "power_in"))
      (node (ref "U5") (pin "6") (pinfunction "REF2_6") (pintype "input"))
      (node (ref "U6") (pin "16") (pinfunction "VCC_16") (pintype "passive"))
      (node (ref "U7") (pin "13") (pinfunction "VDD_13") (pintype "passive"))
      (node (ref "U7") (pin "8") (pinfunction "VLogic_8") (pintype "passive"))
      (node (ref "U8") (pin "3") (pinfunction "VCC_3") (pintype "passive"))
    )
    (net (code "48") (name "5V") (class "Default")
      (node (ref "C20") (pin "2") (pinfunction "2_2") (pintype "passive"))
      (node (ref "C21") (pin "2") (pinfunction "2_2") (pintype "passive"))
      (node (ref "D4") (pin "1") (pinfunction "A_1") (pintype "passive"))
      (node (ref "D6") (pin "2") (pinfunction "K_2") (pintype "passive"))
      (node (ref "L1") (pin "1") (pintype "passive"))
      (node (ref "TPS1") (pin "4") (pinfunction "VIN_4") (pintype "passive"))
      (node (ref "TPS1") (pin "5") (pinfunction "EN_5") (pintype "passive"))
    )
    (net (code "49") (name "9V") (class "Default")
      (node (ref "C23") (pin "2") (pinfunction "2_2") (pintype "passive"))
      (node (ref "C24") (pin "2") (pinfunction "2_2") (pintype "passive"))
      (node (ref "C25") (pin "2") (pinfunction "2_2") (pintype "passive"))
      (node (ref "D5") (pin "2") (pinfunction "K_2") (pintype "passive"))
      (node (ref "OLED1") (pin "2") (pinfunction "VPP_2") (pintype "passive"))
      (node (ref "R19") (pin "2") (pinfunction "2_2") (pintype "passive"))
      (node (ref "TP1") (pin "1") (pintype "passive"))
    )
    (net (code "50") (name "AGND") (class "Default")
      (node (ref "C10") (pin "1") (pinfunction "1_1") (pintype "passive"))
      (node (ref "C5") (pin "1") (pinfunction "1_1") (pintype "passive"))
      (node (ref "C6") (pin "1") (pinfunction "1_1") (pintype "passive"))
      (node (ref "R10") (pin "1") (pinfunction "1_1") (pintype "passive"))
      (node (ref "R16") (pin "1") (pinfunction "1_1") (pintype "passive"))
      (node (ref "U1") (pin "12") (pinfunction "VSSA_12") (pintype "power_in"))
    )
    (net (code "51") (name "AVCC") (class "Default")
      (node (ref "C5") (pin "2") (pinfunction "2_2") (pintype "passive"))
      (node (ref "C6") (pin "2") (pinfunction "2_2") (pintype "passive"))
      (node (ref "R15") (pin "1") (pinfunction "1_1") (pintype "passive"))
      (node (ref "R7") (pin "2") (pinfunction "0_2") (pintype "passive"))
      (node (ref "U1") (pin "13") (pinfunction "VDDA_13") (pintype "power_in"))
    )
    (net (code "52") (name "BAT") (class "Default")
      (node (ref "*1") (pin "1") (pinfunction "VDRAIN_1") (pintype "passive"))
      (node (ref "*1") (pin "13") (pinfunction "VBB_13") (pintype "passive"))
      (node (ref "*1") (pin "14") (pinfunction "VBB_14") (pintype "passive"))
      (node (ref "C28") (pin "2") (pinfunction "2_2") (pintype "passive"))
      (node (ref "C29") (pin "2") (pinfunction "2_2") (pintype "passive"))
      (node (ref "Power2") (pin "1") (pinfunction "DCBUS_1") (pintype "passive"))
      (node (ref "Q1") (pin "D") (pinfunction "D_D") (pintype "passive"))
      (node (ref "Q2") (pin "D") (pinfunction "D_D") (pintype "passive"))
    )
    (net (code "53") (name "GND") (class "Default")
      (node (ref "*1") (pin "17") (pinfunction "GND_17") (pintype "passive"))
      (node (ref "*1") (pin "18") (pinfunction "GND_18") (pintype "passive"))
      (node (ref "*1") (pin "2") (pinfunction "LSS_2") (pintype "passive"))
      (node (ref "*1") (pin "29") (pinfunction "EP_29") (pintype "passive"))
      (node (ref "C1") (pin "1") (pinfunction "1_1") (pintype "passive"))
      (node (ref "C11") (pin "1") (pinfunction "1_1") (pintype "passive"))
      (node (ref "C12") (pin "1") (pinfunction "1_1") (pintype "passive"))
      (node (ref "C13") (pin "2") (pinfunction "2_2") (pintype "passive"))
      (node (ref "C14") (pin "1") (pinfunction "1_1") (pintype "passive"))
      (node (ref "C15") (pin "1") (pinfunction "1_1") (pintype "passive"))
      (node (ref "C16") (pin "1") (pinfunction "1_1") (pintype "passive"))
      (node (ref "C17") (pin "2") (pinfunction "2_2") (pintype "passive"))
      (node (ref "C18") (pin "1") (pinfunction "1_1") (pintype "passive"))
      (node (ref "C19") (pin "1") (pinfunction "1_1") (pintype "passive"))
      (node (ref "C2") (pin "1") (pinfunction "1_1") (pintype "passive"))
      (node (ref "C20") (pin "1") (pinfunction "1_1") (pintype "passive"))
      (node (ref "C21") (pin "1") (pinfunction "1_1") (pintype "passive"))
      (node (ref "C22") (pin "1") (pinfunction "1_1") (pintype "passive"))
      (node (ref "C24") (pin "1") (pinfunction "1_1") (pintype "passive"))
      (node (ref "C25") (pin "1") (pinfunction "1_1") (pintype "passive"))
      (node (ref "C26") (pin "1") (pinfunction "1_1") (pintype "passive"))
      (node (ref "C27") (pin "1") (pinfunction "1_1") (pintype "passive"))
      (node (ref "C28") (pin "1") (pinfunction "1_1") (pintype "passive"))
      (node (ref "C29") (pin "1") (pinfunction "1_1") (pintype "passive"))
      (node (ref "C3") (pin "1") (pinfunction "1_1") (pintype "passive"))
      (node (ref "C32") (pin "1") (pinfunction "1_1") (pintype "passive"))
      (node (ref "C33") (pin "1") (pinfunction "1_1") (pintype "passive"))
      (node (ref "C34") (pin "1") (pinfunction "1_1") (pintype "passive"))
      (node (ref "C35") (pin "2") (pinfunction "2_2") (pintype "passive"))
      (node (ref "C37") (pin "2") (pinfunction "2_2") (pintype "passive"))
      (node (ref "C38") (pin "1") (pinfunction "1_1") (pintype "passive"))
      (node (ref "C39") (pin "1") (pinfunction "1_1") (pintype "passive"))
      (node (ref "C4") (pin "1") (pinfunction "1_1") (pintype "passive"))
      (node (ref "C7") (pin "1") (pinfunction "1_1") (pintype "passive"))
      (node (ref "C8") (pin "1") (pinfunction "1_1") (pintype "passive"))
      (node (ref "C9") (pin "1") (pinfunction "1_1") (pintype "passive"))
      (node (ref "JP1") (pin "5") (pinfunction "5_5") (pintype "passive"))
      (node (ref "JP1") (pin "6") (pinfunction "6_6") (pintype "passive"))
      (node (ref "K1") (pin "2") (pinfunction "2_2") (pintype "passive"))
      (node (ref "OLED1") (pin "12") (pinfunction "VSS_12") (pintype "passive"))
      (node (ref "OLED1") (pin "7") (pinfunction "CS_7") (pintype "passive"))
      (node (ref "OLED1") (pin "9") (pinfunction "DC_9") (pintype "passive"))
      (node (ref "P1") (pin "1") (pinfunction "1_1") (pintype "passive"))
      (node (ref "P1") (pin "SH1") (pinfunction "SH1_SH1") (pintype "passive"))
      (node (ref "P1") (pin "SH2") (pinfunction "SH2_SH2") (pintype "passive"))
      (node (ref "P2") (pin "4") (pinfunction "4_4") (pintype "passive"))
      (node (ref "P2") (pin "SH1") (pinfunction "SH1_SH1") (pintype "passive"))
      (node (ref "P2") (pin "SH2") (pinfunction "SH2_SH2") (pintype "passive"))
      (node (ref "P4") (pin "4") (pinfunction "4_4") (pintype "passive"))
      (node (ref "P4") (pin "SH1") (pinfunction "SH1_SH1") (pintype "passive"))
      (node (ref "P4") (pin "SH2") (pinfunction "SH2_SH2") (pintype "passive"))
      (node (ref "Power2") (pin "2") (pinfunction "PGND_2") (pintype "passive"))
      (node (ref "R16") (pin "2") (pinfunction "2_2") (pintype "passive"))
      (node (ref "R17") (pin "2") (pinfunction "2_2") (pintype "passive"))
      (node (ref "R18") (pin "2") (pinfunction "2_2") (pintype "passive"))
      (node (ref "R2") (pin "1") (pinfunction "1_1") (pintype "passive"))
      (node (ref "R20") (pin "2") (pinfunction "2_2") (pintype "passive"))
      (node (ref "R22") (pin "1") (pinfunction "1_1") (pintype "passive"))
      (node (ref "R32") (pin "1") (pinfunction "1_1") (pintype "passive"))
      (node (ref "R33") (pin "1") (pinfunction "1_1") (pintype "passive"))
      (node (ref "R34") (pin "1") (pinfunction "1_1") (pintype "passive"))
      (node (ref "R35") (pin "1") (pinfunction "1_1") (pintype "passive"))
      (node (ref "R36") (pin "2") (pinfunction "2_2") (pintype "passive"))
      (node (ref "R4") (pin "2") (pinfunction "2_2") (pintype "passive"))
      (node (ref "R8") (pin "1") (pinfunction "1_1") (pintype "passive"))
      (node (ref "TPS1") (pin "2") (pinfunction "GND_2") (pintype "passive"))
      (node (ref "U1") (pin "18") (pinfunction "VSS_18") (pintype "power_in"))
      (node (ref "U1") (pin "63") (pinfunction "VSS_63") (pintype "power_in"))
      (node (ref "U2") (pin "29") (pinfunction "HEAT_TAB_29") (pintype "passive"))
      (node (ref "U2") (pin "3") (pinfunction "GND_3") (pintype "passive"))
      (node (ref "U3") (pin "3") (pinfunction "IN-_3") (pintype "input"))
      (node (ref "U3") (pin "4") (pinfunction "GND_4") (pintype "power_in"))
      (node (ref "U3") (pin "7") (pinfunction "REF1_7") (pintype "input"))
      (node (ref "U4") (pin "2") (pinfunction "GND_2") (pintype "passive"))
      (node (ref "U5") (pin "3") (pinfunction "IN-_3") (pintype "input"))
      (node (ref "U5") (pin "4") (pinfunction "GND_4") (pintype "power_in"))
      (node (ref "U5") (pin "7") (pinfunction "REF1_7") (pintype "input"))
      (node (ref "U6") (pin "8") (pinfunction "GND_8") (pintype "passive"))
      (node (ref "U7") (pin "1") (pinfunction "CLKIN_1") (pintype "passive"))
      (node (ref "U7") (pin "11") (pinfunction "FSYNC_11") (pintype "passive"))
      (node (ref "U7") (pin "18") (pinfunction "GND_18") (pintype "passive"))
      (node (ref "U7") (pin "9") (pinfunction "AD0_9") (pintype "passive"))
      (node (ref "U8") (pin "2") (pinfunction "GND_2") (pintype "passive"))
      (node (ref "USB1") (pin "1") (pinfunction "SH1_1") (pintype "passive"))
      (node (ref "USB1") (pin "2") (pinfunction "SH2_2") (pintype "passive"))
      (node (ref "USB1") (pin "3") (pinfunction "SH3_3") (pintype "passive"))
      (node (ref "USB1") (pin "4") (pinfunction "SH4_4") (pintype "passive"))
      (node (ref "USB1") (pin "A1") (pinfunction "GND_A1") (pintype "passive"))
      (node (ref "USB1") (pin "A12") (pinfunction "GND_A12") (pintype "passive"))
      (node (ref "USB1") (pin "B1") (pinfunction "GND_B1") (pintype "passive"))
      (node (ref "USB1") (pin "B12") (pinfunction "GND_B12") (pintype "passive"))
      (node (ref "X1") (pin "2") (pinfunction "GND_2") (pintype "passive"))
    )
    (net (code "54") (name "Net-(*1-CA)") (class "Default")
      (node (ref "*1") (pin "9") (pinfunction "CA_9") (pintype "passive"))
      (node (ref "C31") (pin "1") (pinfunction "1_1") (pintype "passive"))
    )
    (net (code "55") (name "Net-(*1-CB)") (class "Default")
      (node (ref "*1") (pin "6") (pinfunction "CB_6") (pintype "passive"))
      (node (ref "C36") (pin "2") (pinfunction "2_2") (pintype "passive"))
    )
    (net (code "56") (name "Net-(*1-CP1)") (class "Default")
      (node (ref "*1") (pin "16") (pinfunction "CP1_16") (pintype "passive"))
      (node (ref "C30") (pin "1") (pinfunction "1_1") (pintype "passive"))
    )
    (net (code "57") (name "Net-(*1-CP2)") (class "Default")
      (node (ref "*1") (pin "15") (pinfunction "CP2_15") (pintype "passive"))
      (node (ref "C30") (pin "2") (pinfunction "2_2") (pintype "passive"))
    )
    (net (code "58") (name "Net-(*1-FF1)") (class "Default")
      (node (ref "*1") (pin "25") (pinfunction "FF1_25") (pintype "passive"))
      (node (ref "R28") (pin "1") (pinfunction "1_1") (pintype "passive"))
    )
    (net (code "59") (name "Net-(*1-FF2)") (class "Default")
      (node (ref "*1") (pin "26") (pinfunction "FF2_26") (pintype "passive"))
      (node (ref "R27") (pin "1") (pinfunction "1_1") (pintype "passive"))
    )
    (net (code "60") (name "Net-(*1-RDEAD)") (class "Default")
      (node (ref "*1") (pin "27") (pinfunction "RDEAD_27") (pintype "passive"))
      (node (ref "R32") (pin "2") (pinfunction "2_2") (pintype "passive"))
    )
    (net (code "61") (name "Net-(*1-VDSTH)") (class "Default")
      (node (ref "*1") (pin "28") (pinfunction "VDSTH_28") (pintype "passive"))
      (node (ref "R33") (pin "2") (pinfunction "2_2") (pintype "passive"))
    )
    (net (code "62") (name "Net-(*1-VREG-Pad7)") (class "Default")
      (node (ref "*1") (pin "7") (pinfunction "VREG_7") (pintype "passive"))
      (node (ref "C33") (pin "2") (pinfunction "2_2") (pintype "passive"))
    )
    (net (code "63") (name "Net-(*1-VREG-Pad8)") (class "Default")
      (node (ref "*1") (pin "8") (pinfunction "VREG_8") (pintype "passive"))
      (node (ref "C32") (pin "2") (pinfunction "2_2") (pintype "passive"))
    )
    (net (code "64") (name "Net-(*1-VS)") (class "Default")
      (node (ref "*1") (pin "20") (pinfunction "VS_20") (pintype "passive"))
      (node (ref "C34") (pin "2") (pinfunction "2_2") (pintype "passive"))
      (node (ref "R27") (pin "2") (pinfunction "2_2") (pintype "passive"))
      (node (ref "R28") (pin "2") (pinfunction "2_2") (pintype "passive"))
    )
    (net (code "65") (name "Net-(D1-K)") (class "Default")
      (node (ref "D1") (pin "2") (pinfunction "K_2") (pintype "passive"))
      (node (ref "R5") (pin "1") (pinfunction "1_1") (pintype "passive"))
    )
    (net (code "66") (name "Net-(D2-K)") (class "Default")
      (node (ref "D2") (pin "2") (pinfunction "K_2") (pintype "passive"))
      (node (ref "R6") (pin "1") (pinfunction "1_1") (pintype "passive"))
    )
    (net (code "67") (name "Net-(D3-K)") (class "Default")
      (node (ref "D3") (pin "2") (pinfunction "K_2") (pintype "passive"))
      (node (ref "R17") (pin "1") (pinfunction "1_1") (pintype "passive"))
    )
    (net (code "68") (name "Net-(D4-K)") (class "Default")
      (node (ref "D4") (pin "2") (pinfunction "K_2") (pintype "passive"))
      (node (ref "R18") (pin "1") (pinfunction "1_1") (pintype "passive"))
    )
    (net (code "69") (name "Net-(D5-A)") (class "Default")
      (node (ref "D5") (pin "1") (pinfunction "A_1") (pintype "passive"))
      (node (ref "L1") (pin "2") (pinfunction "2_2") (pintype "passive"))
      (node (ref "TPS1") (pin "3") (pinfunction "FB_3") (pintype "passive"))
    )
    (net (code "70") (name "Net-(OLED1-IM1)") (class "Default")
      (node (ref "OLED1") (pin "5") (pinfunction "IM1_5") (pintype "passive"))
      (node (ref "R21") (pin "1") (pinfunction "1_1") (pintype "passive"))
    )
    (net (code "71") (name "Net-(OLED1-IREF)") (class "Default")
      (node (ref "OLED1") (pin "6") (pinfunction "IREF_6") (pintype "passive"))
      (node (ref "R20") (pin "1") (pinfunction "1_1") (pintype "passive"))
    )
    (net (code "72") (name "Net-(OLED1-VCCOMH)") (class "Default")
      (node (ref "C26") (pin "2") (pinfunction "2_2") (pintype "passive"))
      (node (ref "OLED1") (pin "3") (pinfunction "VCCOMH_3") (pintype "passive"))
    )
    (net (code "73") (name "Net-(Q1-PadG)") (class "Default")
      (node (ref "Q1") (pin "G") (pinfunction "G_G") (pintype "passive"))
      (node (ref "R25") (pin "2") (pinfunction "2_2") (pintype "passive"))
    )
    (net (code "74") (name "Net-(Q2-PadG)") (class "Default")
      (node (ref "Q2") (pin "G") (pinfunction "G_G") (pintype "passive"))
      (node (ref "R26") (pin "2") (pinfunction "2_2") (pintype "passive"))
    )
    (net (code "75") (name "Net-(Q3-PadG)") (class "Default")
      (node (ref "Q3") (pin "G") (pinfunction "G_G") (pintype "passive"))
      (node (ref "R29") (pin "2") (pinfunction "2_2") (pintype "passive"))
    )
    (net (code "76") (name "Net-(Q4-PadG)") (class "Default")
      (node (ref "Q4") (pin "G") (pinfunction "G_G") (pintype "passive"))
      (node (ref "R30") (pin "2") (pinfunction "2_2") (pintype "passive"))
    )
    (net (code "77") (name "Net-(TPS1-SW)") (class "Default")
      (node (ref "C23") (pin "1") (pinfunction "1_1") (pintype "passive"))
      (node (ref "R19") (pin "1") (pinfunction "1_1") (pintype "passive"))
      (node (ref "R22") (pin "2") (pinfunction "2_2") (pintype "passive"))
      (node (ref "TPS1") (pin "1") (pinfunction "SW_1") (pintype "passive"))
    )
    (net (code "78") (name "Net-(U1A-VCAP_1)") (class "Default")
      (node (ref "C12") (pin "2") (pinfunction "2_2") (pintype "passive"))
      (node (ref "U1") (pin "31") (pinfunction "VCAP_1_31") (pintype "power_in"))
    )
    (net (code "79") (name "Net-(U1A-VCAP_2)") (class "Default")
      (node (ref "C11") (pin "2") (pinfunction "2_2") (pintype "passive"))
      (node (ref "U1") (pin "47") (pinfunction "VCAP_2_47") (pintype "power_in"))
    )
    (net (code "80") (name "Net-(U2-*RST)") (class "Default")
      (node (ref "R1") (pin "2") (pinfunction "2_2") (pintype "passive"))
      (node (ref "U2") (pin "9") (pinfunction "*RST_9") (pintype "passive"))
    )
    (net (code "81") (name "Net-(U2-TXD)") (class "Default")
      (node (ref "R3") (pin "2") (pinfunction "2_2") (pintype "passive"))
      (node (ref "U2") (pin "26") (pinfunction "TXD_26") (pintype "passive"))
    )
    (net (code "82") (name "Net-(U3-OUT)") (class "Default")
      (node (ref "R11") (pin "1") (pinfunction "1_1") (pintype "passive"))
      (node (ref "U3") (pin "8") (pinfunction "OUT_8") (pintype "output"))
    )
    (net (code "83") (name "Net-(U4-BYPASS)") (class "Default")
      (node (ref "C17") (pin "1") (pinfunction "1_1") (pintype "passive"))
      (node (ref "U4") (pin "4") (pinfunction "BYPASS_4") (pintype "passive"))
    )
    (net (code "84") (name "Net-(U5-OUT)") (class "Default")
      (node (ref "R13") (pin "1") (pinfunction "1_1") (pintype "passive"))
      (node (ref "U5") (pin "8") (pinfunction "OUT_8") (pintype "output"))
    )
    (net (code "85") (name "Net-(U7-CPOUT)") (class "Default")
      (node (ref "C38") (pin "2") (pinfunction "2_2") (pintype "passive"))
      (node (ref "U7") (pin "20") (pinfunction "CPOUT_20") (pintype "passive"))
    )
    (net (code "86") (name "Net-(U7-REGOUT)") (class "Default")
      (node (ref "C37") (pin "1") (pinfunction "1_1") (pintype "passive"))
      (node (ref "U7") (pin "10") (pinfunction "REGOUT_10") (pintype "passive"))
    )
    (net (code "87") (name "Net-(U8-Vref)") (class "Default")
      (node (ref "TP2") (pin "1") (pintype "passive"))
      (node (ref "U8") (pin "5") (pinfunction "Vref_5") (pintype "passive"))
    )
    (net (code "88") (name "Net-(USB1-CC1)") (class "Default")
      (node (ref "R36") (pin "1") (pinfunction "1_1") (pintype "passive"))
      (node (ref "USB1") (pin "A5") (pinfunction "CC1_A5") (pintype "passive"))
    )
    (net (code "89") (name "Net-(USB1-CC2)") (class "Default")
      (node (ref "R4") (pin "1") (pinfunction "1_1") (pintype "passive"))
      (node (ref "USB1") (pin "B5") (pinfunction "CC2_B5") (pintype "passive"))
    )
    (net (code "90") (name "VBUS") (class "Default")
      (node (ref "D6") (pin "1") (pinfunction "A_1") (pintype "passive"))
      (node (ref "R1") (pin "1") (pinfunction "1_1") (pintype "passive"))
      (node (ref "U2") (pin "7") (pinfunction "REGIN_7") (pintype "passive"))
      (node (ref "U2") (pin "8") (pinfunction "VBUS_8") (pintype "passive"))
      (node (ref "U4") (pin "1") (pinfunction "VIN_1") (pintype "passive"))
      (node (ref "U4") (pin "3") (pinfunction "ON/OFF_3") (pintype "passive"))
      (node (ref "USB1") (pin "A4") (pinfunction "VBUS_A4") (pintype "passive"))
      (node (ref "USB1") (pin "A9") (pinfunction "VBUS_A9") (pintype "passive"))
      (node (ref "USB1") (pin "B4") (pinfunction "VBUS_B4") (pintype "passive"))
      (node (ref "USB1") (pin "B9") (pinfunction "VBUS_B9") (pintype "passive"))
    )
    (net (code "91") (name "unconnected-(OLED1-NC1-Pad1)") (class "Default")
      (node (ref "OLED1") (pin "1") (pinfunction "NC1_1") (pintype "passive"))
    )
    (net (code "92") (name "unconnected-(OLED1-NC2-Pad13)") (class "Default")
      (node (ref "OLED1") (pin "13") (pinfunction "NC2_13") (pintype "passive"))
    )
    (net (code "93") (name "unconnected-(OLED1-RES-Pad8)") (class "Default")
      (node (ref "OLED1") (pin "8") (pinfunction "RES_8") (pintype "passive"))
    )
    (net (code "94") (name "unconnected-(U1A-PA6-Pad22)") (class "Default")
      (node (ref "U1") (pin "22") (pinfunction "PA6_22") (pintype "bidirectional"))
    )
    (net (code "95") (name "unconnected-(U1A-PA15(JTDI)-Pad50)") (class "Default")
      (node (ref "U1") (pin "50") (pinfunction "PA15(JTDI)_50") (pintype "bidirectional"))
    )
    (net (code "96") (name "unconnected-(U1A-PB0-Pad26)") (class "Default")
      (node (ref "U1") (pin "26") (pinfunction "PB0_26") (pintype "bidirectional"))
    )
    (net (code "97") (name "unconnected-(U1A-PB1-Pad27)") (class "Default")
      (node (ref "U1") (pin "27") (pinfunction "PB1_27") (pintype "bidirectional"))
    )
    (net (code "98") (name "unconnected-(U1A-PB4(NJTRST)-Pad56)") (class "Default")
      (node (ref "U1") (pin "56") (pinfunction "PB4(NJTRST)_56") (pintype "bidirectional"))
    )
    (net (code "99") (name "unconnected-(U1A-PB5-Pad57)") (class "Default")
      (node (ref "U1") (pin "57") (pinfunction "PB5_57") (pintype "bidirectional"))
    )
    (net (code "100") (name "unconnected-(U1A-PB8-Pad61)") (class "Default")
      (node (ref "U1") (pin "61") (pinfunction "PB8_61") (pintype "bidirectional"))
    )
    (net (code "101") (name "unconnected-(U1A-PB9-Pad62)") (class "Default")
      (node (ref "U1") (pin "62") (pinfunction "PB9_62") (pintype "bidirectional"))
    )
    (net (code "102") (name "unconnected-(U1A-PB12-Pad33)") (class "Default")
      (node (ref "U1") (pin "33") (pinfunction "PB12_33") (pintype "bidirectional"))
    )
    (net (code "103") (name "unconnected-(U1A-PB13-Pad34)") (class "Default")
      (node (ref "U1") (pin "34") (pinfunction "PB13_34") (pintype "bidirectional"))
    )
    (net (code "104") (name "unconnected-(U1A-PB14-Pad35)") (class "Default")
      (node (ref "U1") (pin "35") (pinfunction "PB14_35") (pintype "bidirectional"))
    )
    (net (code "105") (name "unconnected-(U1A-PB15-Pad36)") (class "Default")
      (node (ref "U1") (pin "36") (pinfunction "PB15_36") (pintype "bidirectional"))
    )
    (net (code "106") (name "unconnected-(U1A-PC5-Pad25)") (class "Default")
      (node (ref "U1") (pin "25") (pinfunction "PC5_25") (pintype "bidirectional"))
    )
    (net (code "107") (name "unconnected-(U1A-PC7-Pad38)") (class "Default")
      (node (ref "U1") (pin "38") (pinfunction "PC7_38") (pintype "bidirectional"))
    )
    (net (code "108") (name "unconnected-(U1A-PC8-Pad39)") (class "Default")
      (node (ref "U1") (pin "39") (pinfunction "PC8_39") (pintype "bidirectional"))
    )
    (net (code "109") (name "unconnected-(U1A-PC9-Pad40)") (class "Default")
      (node (ref "U1") (pin "40") (pinfunction "PC9_40") (pintype "bidirectional"))
    )
    (net (code "110") (name "unconnected-(U1A-PC10-Pad51)") (class "Default")
      (node (ref "U1") (pin "51") (pinfunction "PC10_51") (pintype "bidirectional"))
    )
    (net (code "111") (name "unconnected-(U1A-PC11-Pad52)") (class "Default")
      (node (ref "U1") (pin "52") (pinfunction "PC11_52") (pintype "bidirectional"))
    )
    (net (code "112") (name "unconnected-(U1A-PC12-Pad53)") (class "Default")
      (node (ref "U1") (pin "53") (pinfunction "PC12_53") (pintype "bidirectional"))
    )
    (net (code "113") (name "unconnected-(U1A-PC13-Pad2)") (class "Default")
      (node (ref "U1") (pin "2") (pinfunction "PC13_2") (pintype "bidirectional"))
    )
    (net (code "114") (name "unconnected-(U1A-PC14-OSC32_IN(PC14)-Pad3)") (class "Default")
      (node (ref "U1") (pin "3") (pinfunction "PC14-OSC32_IN(PC14)_3") (pintype "bidirectional"))
    )
    (net (code "115") (name "unconnected-(U1A-PC15-OSC32_OUT(PC15)-Pad4)") (class "Default")
      (node (ref "U1") (pin "4") (pinfunction "PC15-OSC32_OUT(PC15)_4") (pintype "bidirectional"))
    )
    (net (code "116") (name "unconnected-(U1A-PD2-Pad54)") (class "Default")
      (node (ref "U1") (pin "54") (pinfunction "PD2_54") (pintype "bidirectional"))
    )
    (net (code "117") (name "unconnected-(U2-*SUSPEND-Pad11)") (class "Default")
      (node (ref "U2") (pin "11") (pinfunction "*SUSPEND_11") (pintype "passive"))
    )
    (net (code "118") (name "unconnected-(U2-CTS-Pad23)") (class "Default")
      (node (ref "U2") (pin "23") (pinfunction "CTS_23") (pintype "passive"))
    )
    (net (code "119") (name "unconnected-(U2-DCD-Pad1)") (class "Default")
      (node (ref "U2") (pin "1") (pinfunction "DCD_1") (pintype "passive"))
    )
    (net (code "120") (name "unconnected-(U2-DSR-Pad27)") (class "Default")
      (node (ref "U2") (pin "27") (pinfunction "DSR_27") (pintype "passive"))
    )
    (net (code "121") (name "unconnected-(U2-DTR-Pad28)") (class "Default")
      (node (ref "U2") (pin "28") (pinfunction "DTR_28") (pintype "passive"))
    )
    (net (code "122") (name "unconnected-(U2-NC-Pad10)") (class "Default")
      (node (ref "U2") (pin "10") (pinfunction "NC_10") (pintype "passive"))
    )
    (net (code "123") (name "unconnected-(U2-NC-Pad13)") (class "Default")
      (node (ref "U2") (pin "13") (pinfunction "NC_13") (pintype "passive"))
    )
    (net (code "124") (name "unconnected-(U2-NC-Pad14)") (class "Default")
      (node (ref "U2") (pin "14") (pinfunction "NC_14") (pintype "passive"))
    )
    (net (code "125") (name "unconnected-(U2-NC-Pad15)") (class "Default")
      (node (ref "U2") (pin "15") (pinfunction "NC_15") (pintype "passive"))
    )
    (net (code "126") (name "unconnected-(U2-NC-Pad16)") (class "Default")
      (node (ref "U2") (pin "16") (pinfunction "NC_16") (pintype "passive"))
    )
    (net (code "127") (name "unconnected-(U2-NC-Pad17)") (class "Default")
      (node (ref "U2") (pin "17") (pinfunction "NC_17") (pintype "passive"))
    )
    (net (code "128") (name "unconnected-(U2-NC-Pad18)") (class "Default")
      (node (ref "U2") (pin "18") (pinfunction "NC_18") (pintype "passive"))
    )
    (net (code "129") (name "unconnected-(U2-NC-Pad19)") (class "Default")
      (node (ref "U2") (pin "19") (pinfunction "NC_19") (pintype "passive"))
    )
    (net (code "130") (name "unconnected-(U2-NC-Pad20)") (class "Default")
      (node (ref "U2") (pin "20") (pinfunction "NC_20") (pintype "passive"))
    )
    (net (code "131") (name "unconnected-(U2-NC-Pad21)") (class "Default")
      (node (ref "U2") (pin "21") (pinfunction "NC_21") (pintype "passive"))
    )
    (net (code "132") (name "unconnected-(U2-NC-Pad22)") (class "Default")
      (node (ref "U2") (pin "22") (pinfunction "NC_22") (pintype "passive"))
    )
    (net (code "133") (name "unconnected-(U2-RI-Pad2)") (class "Default")
      (node (ref "U2") (pin "2") (pinfunction "RI_2") (pintype "passive"))
    )
    (net (code "134") (name "unconnected-(U2-RTS-Pad24)") (class "Default")
      (node (ref "U2") (pin "24") (pinfunction "RTS_24") (pintype "passive"))
    )
    (net (code "135") (name "unconnected-(U2-SUSPEND-Pad12)") (class "Default")
      (node (ref "U2") (pin "12") (pinfunction "SUSPEND_12") (pintype "passive"))
    )
    (net (code "136") (name "unconnected-(U2-VDD-Pad6)") (class "Default")
      (node (ref "U2") (pin "6") (pinfunction "VDD_6") (pintype "passive"))
    )
    (net (code "137") (name "unconnected-(U6-3A-Pad10)") (class "Default")
      (node (ref "U6") (pin "10") (pinfunction "3A_10") (pintype "passive"))
    )
    (net (code "138") (name "unconnected-(U6-3B-Pad9)") (class "Default")
      (node (ref "U6") (pin "9") (pinfunction "3B_9") (pintype "passive"))
    )
    (net (code "139") (name "unconnected-(U6-3Y-Pad11)") (class "Default")
      (node (ref "U6") (pin "11") (pinfunction "3Y_11") (pintype "passive"))
    )
    (net (code "140") (name "unconnected-(U6-4A-Pad14)") (class "Default")
      (node (ref "U6") (pin "14") (pinfunction "4A_14") (pintype "passive"))
    )
    (net (code "141") (name "unconnected-(U6-4B-Pad15)") (class "Default")
      (node (ref "U6") (pin "15") (pinfunction "4B_15") (pintype "passive"))
    )
    (net (code "142") (name "unconnected-(U6-4Y-Pad13)") (class "Default")
      (node (ref "U6") (pin "13") (pinfunction "4Y_13") (pintype "passive"))
    )
    (net (code "143") (name "unconnected-(U6-G-Pad4)") (class "Default")
      (node (ref "U6") (pin "4") (pinfunction "G_4") (pintype "passive"))
    )
    (net (code "144") (name "unconnected-(U6-~{G}-Pad12)") (class "Default")
      (node (ref "U6") (pin "12") (pinfunction "~{G}_12") (pintype "passive"))
    )
    (net (code "145") (name "unconnected-(U7-A_CL-Pad7)") (class "Default")
      (node (ref "U7") (pin "7") (pinfunction "A_CL_7") (pintype "passive"))
    )
    (net (code "146") (name "unconnected-(U7-A_DA-Pad6)") (class "Default")
      (node (ref "U7") (pin "6") (pinfunction "A_DA_6") (pintype "passive"))
    )
    (net (code "147") (name "unconnected-(U7-CLKOUT-Pad22)") (class "Default")
      (node (ref "U7") (pin "22") (pinfunction "CLKOUT_22") (pintype "passive"))
    )
    (net (code "148") (name "unconnected-(U7-INT-Pad12)") (class "Default")
      (node (ref "U7") (pin "12") (pinfunction "INT_12") (pintype "passive"))
    )
    (net (code "149") (name "unconnected-(U7-NC-Pad2)") (class "Default")
      (node (ref "U7") (pin "2") (pinfunction "NC_2") (pintype "passive"))
    )
    (net (code "150") (name "unconnected-(U7-NC-Pad3)") (class "Default")
      (node (ref "U7") (pin "3") (pinfunction "NC_3") (pintype "passive"))
    )
    (net (code "151") (name "unconnected-(U7-NC-Pad4)") (class "Default")
      (node (ref "U7") (pin "4") (pinfunction "NC_4") (pintype "passive"))
    )
    (net (code "152") (name "unconnected-(U7-NC-Pad5)") (class "Default")
      (node (ref "U7") (pin "5") (pinfunction "NC_5") (pintype "passive"))
    )
    (net (code "153") (name "unconnected-(U7-NC-Pad14)") (class "Default")
      (node (ref "U7") (pin "14") (pinfunction "NC_14") (pintype "passive"))
    )
    (net (code "154") (name "unconnected-(U7-NC-Pad15)") (class "Default")
      (node (ref "U7") (pin "15") (pinfunction "NC_15") (pintype "passive"))
    )
    (net (code "155") (name "unconnected-(U7-NC-Pad16)") (class "Default")
      (node (ref "U7") (pin "16") (pinfunction "NC_16") (pintype "passive"))
    )
    (net (code "156") (name "unconnected-(U7-NC-Pad17)") (class "Default")
      (node (ref "U7") (pin "17") (pinfunction "NC_17") (pintype "passive"))
    )
    (net (code "157") (name "unconnected-(U7-RESV-Pad19)") (class "Default")
      (node (ref "U7") (pin "19") (pinfunction "RESV_19") (pintype "passive"))
    )
    (net (code "158") (name "unconnected-(U7-RESV-Pad21)") (class "Default")
      (node (ref "U7") (pin "21") (pinfunction "RESV_21") (pintype "passive"))
    )
    (net (code "159") (name "unconnected-(U8-EP-Pad9)") (class "Default")
      (node (ref "U8") (pin "9") (pinfunction "EP_9") (pintype "passive"))
    )
    (net (code "160") (name "unconnected-(USB1-RX1+-PadB11)") (class "Default")
      (node (ref "USB1") (pin "B11") (pinfunction "RX1+_B11") (pintype "passive"))
    )
    (net (code "161") (name "unconnected-(USB1-RX1--PadB10)") (class "Default")
      (node (ref "USB1") (pin "B10") (pinfunction "RX1-_B10") (pintype "passive"))
    )
    (net (code "162") (name "unconnected-(USB1-RX2+-PadA11)") (class "Default")
      (node (ref "USB1") (pin "A11") (pinfunction "RX2+_A11") (pintype "passive"))
    )
    (net (code "163") (name "unconnected-(USB1-RX2--PadA10)") (class "Default")
      (node (ref "USB1") (pin "A10") (pinfunction "RX2-_A10") (pintype "passive"))
    )
    (net (code "164") (name "unconnected-(USB1-SBU1-PadA8)") (class "Default")
      (node (ref "USB1") (pin "A8") (pinfunction "SBU1_A8") (pintype "passive"))
    )
    (net (code "165") (name "unconnected-(USB1-SBU2-PadB8)") (class "Default")
      (node (ref "USB1") (pin "B8") (pinfunction "SBU2_B8") (pintype "passive"))
    )
    (net (code "166") (name "unconnected-(USB1-TX1+-PadA2)") (class "Default")
      (node (ref "USB1") (pin "A2") (pinfunction "TX1+_A2") (pintype "passive"))
    )
    (net (code "167") (name "unconnected-(USB1-TX1--PadA3)") (class "Default")
      (node (ref "USB1") (pin "A3") (pinfunction "TX1-_A3") (pintype "passive"))
    )
    (net (code "168") (name "unconnected-(USB1-TX2+-PadB2)") (class "Default")
      (node (ref "USB1") (pin "B2") (pinfunction "TX2+_B2") (pintype "passive"))
    )
    (net (code "169") (name "unconnected-(USB1-TX2--PadB3)") (class "Default")
      (node (ref "USB1") (pin "B3") (pinfunction "TX2-_B3") (pintype "passive"))
    )
  )
)
